# GPS_radiologger_v20_CAM_M8Q_Programmer.net
KiCad netlist of a schematic drawn in EAGLE
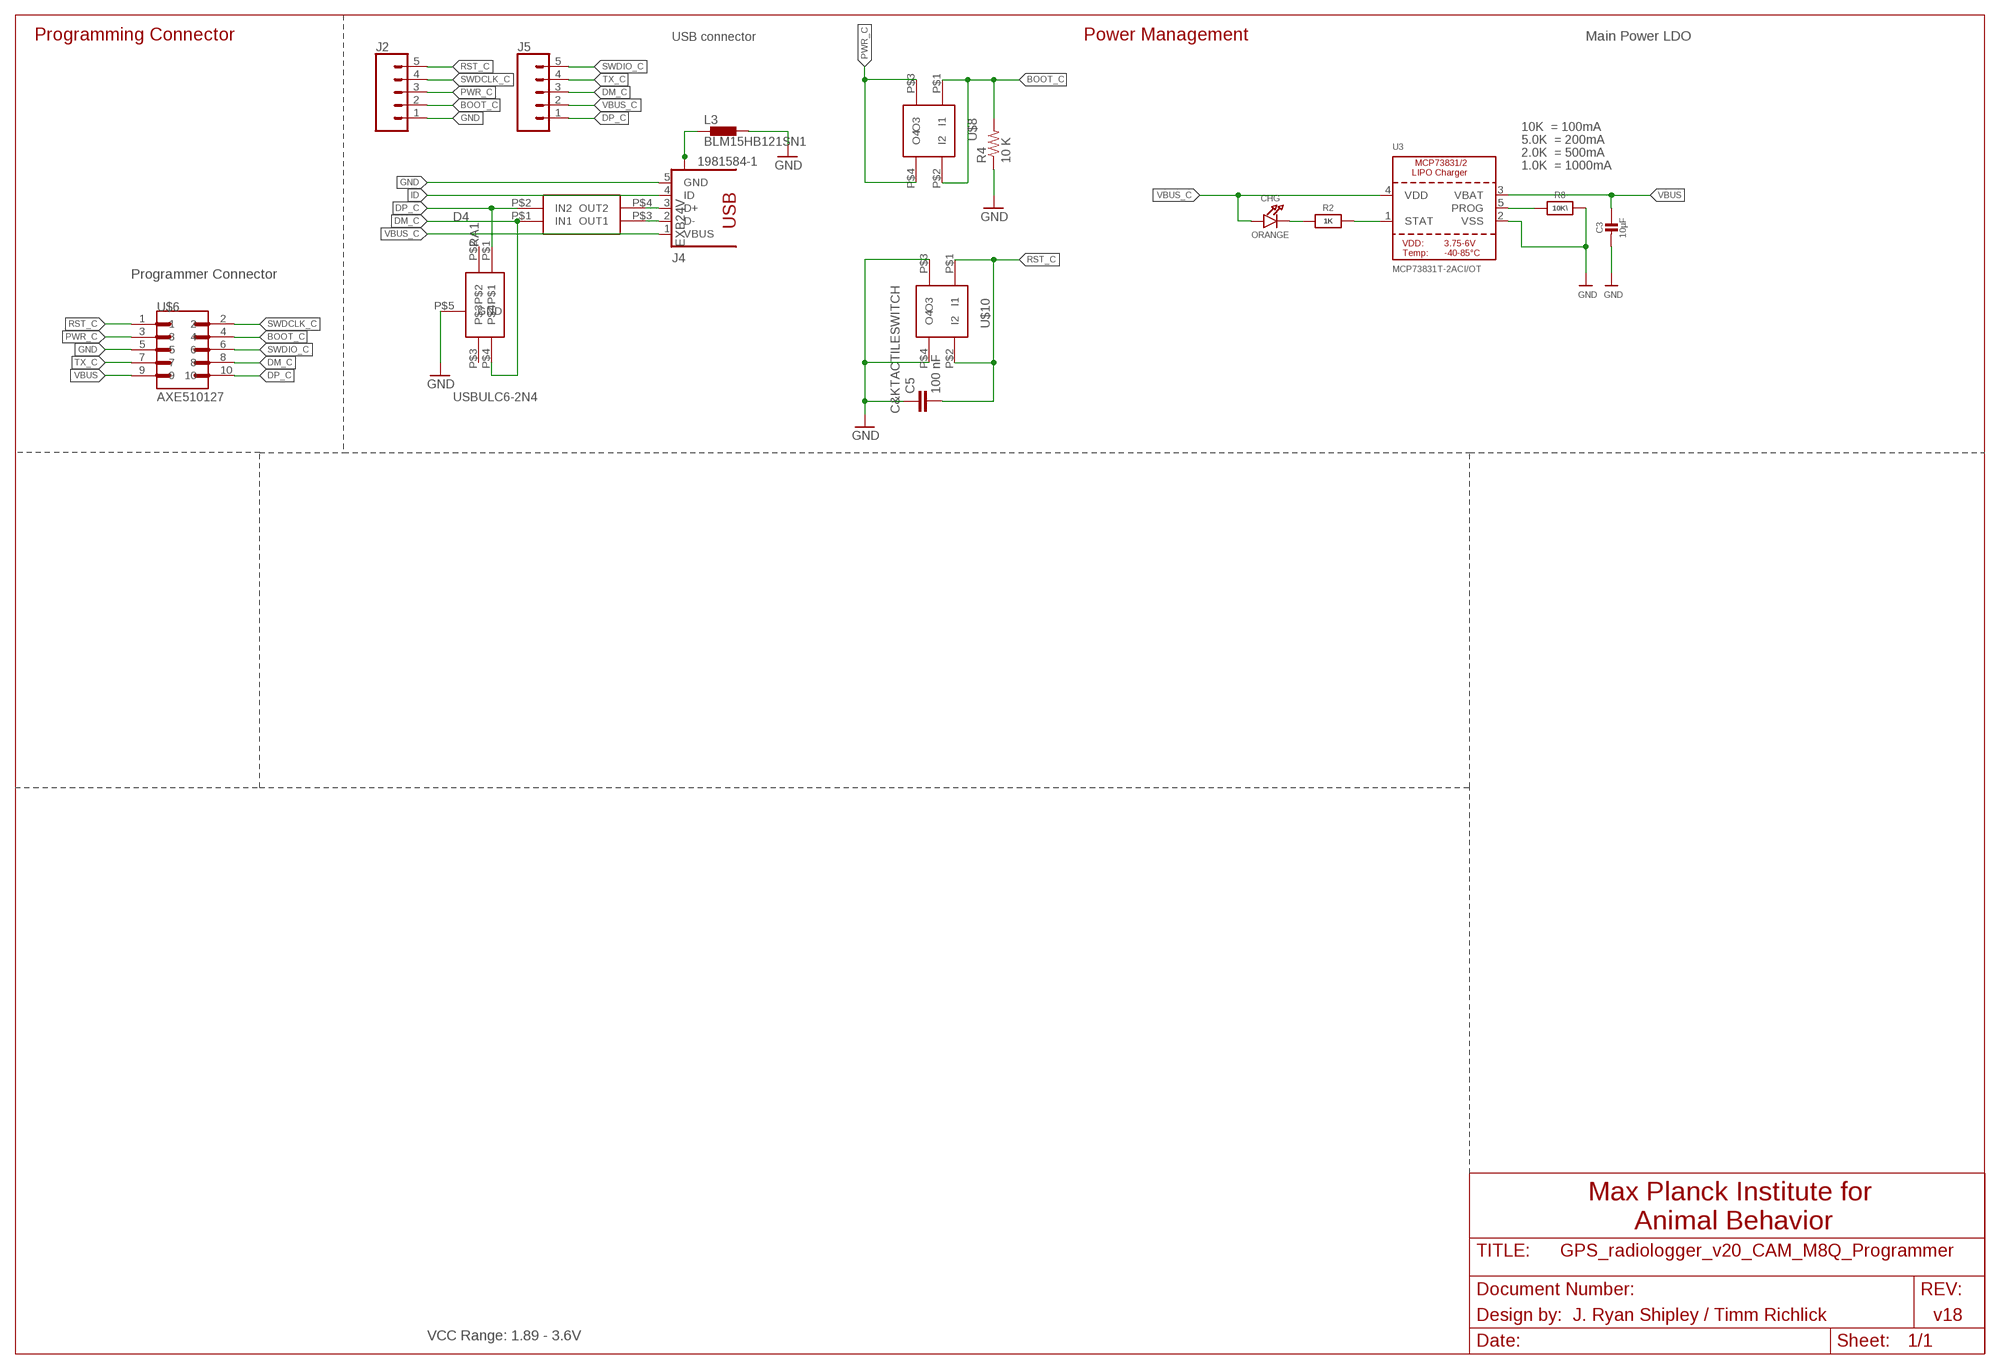
[diagram p0: schematic, sheet 1]

(export (version "E")
  (design (tool "Eeschema 10.0.6"))
  (components
    (comp (ref "C3")
      (value "10µF")
      (footprint "eagle-import:0805-NO")
      (libsource (lib "eagle-import") (part "CAP_CERAMIC0805-NOOUTLINE"))
    )
    (comp (ref "C5")
      (value "100 nF")
      (footprint "eagle-import:0402-CAP")
      (libsource (lib "eagle-import") (part "0402CAP.KW"))
    )
    (comp (ref "CHG")
      (value "ORANGE")
      (footprint "eagle-import:CHIPLED_0805_NOOUTLINE")
      (libsource (lib "eagle-import") (part "LED0805_NOOUTLINE"))
    )
    (comp (ref "D4")
      (value "USBULC6-2N4")
      (footprint "eagle-import:USBULC6-2N4")
      (libsource (lib "eagle-import") (part "USBULC6-2N4"))
    )
    (comp (ref "J2")
      (value "CONN_05")
      (footprint "eagle-import:1X05")
      (libsource (lib "eagle-import") (part "CONN_05"))
    )
    (comp (ref "J4")
      (value "1981584-1")
      (footprint "eagle-import:1981584-1")
      (fields (field (name "MF") "Hirose") (field (name "MPN") "ZX62-AB-5PA(11) "))
      (libsource (lib "eagle-import") (part "1981584-1"))
    )
    (comp (ref "J5")
      (value "CONN_05")
      (footprint "eagle-import:1X05")
      (libsource (lib "eagle-import") (part "CONN_05"))
    )
    (comp (ref "L3")
      (value "BLM15HB121SN1")
      (footprint "eagle-import:0402")
      (libsource (lib "eagle-import") (part "BLM15HB121SN1"))
    )
    (comp (ref "R2")
      (value "1K")
      (footprint "eagle-import:0603-NO")
      (libsource (lib "eagle-import") (part "RESISTOR_0603_NOOUT"))
    )
    (comp (ref "R4")
      (value "10 K")
      (footprint "eagle-import:0402-RES")
      (libsource (lib "eagle-import") (part "0402RES.KW"))
    )
    (comp (ref "R8")
      (value "10K\\")
      (footprint "eagle-import:0603-NO")
      (libsource (lib "eagle-import") (part "RESISTOR_0603_NOOUT"))
    )
    (comp (ref "RA1")
      (value "EXB24V")
      (footprint "eagle-import:EXB24V")
      (libsource (lib "eagle-import") (part "EXB24V"))
    )
    (comp (ref "U$6")
      (value "AXE510127")
      (footprint "eagle-import:AXE510127")
      (libsource (lib "eagle-import") (part "AXE510127"))
    )
    (comp (ref "U$8")
      (value "C&KTACTILESWITCH")
      (footprint "eagle-import:C&KTACTILESWITCH")
      (libsource (lib "eagle-import") (part "C&KTACTILESWITCH"))
    )
    (comp (ref "U$10")
      (value "C&KTACTILESWITCH")
      (footprint "eagle-import:C&KTACTILESWITCH")
      (libsource (lib "eagle-import") (part "C&KTACTILESWITCH"))
    )
    (comp (ref "U3")
      (value "MCP73831T-2ACI/OT")
      (footprint "eagle-import:SOT23-5")
      (libsource (lib "eagle-import") (part "MCP73831/2"))
    )
  )
  (nets
    (net (code "1") (name "BOOT_C") (class "Default")
      (node (ref "J2") (pin "2") (pinfunction "2_2") (pintype "passive"))
      (node (ref "R4") (pin "2") (pinfunction "2_2") (pintype "passive"))
      (node (ref "U$6") (pin "4") (pinfunction "4_4") (pintype "passive"))
      (node (ref "U$8") (pin "P$1") (pinfunction "I1_P$1") (pintype "bidirectional"))
      (node (ref "U$8") (pin "P$2") (pinfunction "I2_P$2") (pintype "bidirectional"))
    )
    (net (code "2") (name "DM_C") (class "Default")
      (node (ref "D4") (pin "P$4") (pinfunction "P$4_P$4") (pintype "bidirectional"))
      (node (ref "J5") (pin "3") (pinfunction "3_3") (pintype "passive"))
      (node (ref "RA1") (pin "P$1") (pinfunction "IN1_P$1") (pintype "bidirectional"))
      (node (ref "U$6") (pin "8") (pinfunction "8_8") (pintype "passive"))
    )
    (net (code "3") (name "DP_C") (class "Default")
      (node (ref "D4") (pin "P$1") (pinfunction "P$1_P$1") (pintype "bidirectional"))
      (node (ref "J5") (pin "1") (pinfunction "1_1") (pintype "passive"))
      (node (ref "RA1") (pin "P$2") (pinfunction "IN2_P$2") (pintype "bidirectional"))
      (node (ref "U$6") (pin "10") (pinfunction "10_10") (pintype "passive"))
    )
    (net (code "4") (name "GND") (class "Default")
      (node (ref "C3") (pin "2") (pinfunction "2_2") (pintype "passive"))
      (node (ref "C5") (pin "1") (pinfunction "1_1") (pintype "passive"))
      (node (ref "D4") (pin "P$5") (pinfunction "GND_P$5") (pintype "bidirectional"))
      (node (ref "J2") (pin "1") (pinfunction "1_1") (pintype "passive"))
      (node (ref "J4") (pin "5") (pinfunction "GND_5") (pintype "passive"))
      (node (ref "L3") (pin "2") (pinfunction "2_2") (pintype "passive"))
      (node (ref "R4") (pin "1") (pinfunction "1_1") (pintype "passive"))
      (node (ref "R8") (pin "2") (pinfunction "2_2") (pintype "passive"))
      (node (ref "U$10") (pin "P$3") (pinfunction "O3_P$3") (pintype "bidirectional"))
      (node (ref "U$10") (pin "P$4") (pinfunction "O4_P$4") (pintype "bidirectional"))
      (node (ref "U$6") (pin "5") (pinfunction "5_5") (pintype "passive"))
      (node (ref "U3") (pin "2") (pinfunction "VSS_2") (pintype "power_in"))
    )
    (net (code "5") (name "ID") (class "Default")
      (node (ref "J4") (pin "4") (pinfunction "ID_4") (pintype "passive"))
    )
    (net (code "6") (name "Net-(CHG-PadC)") (class "Default")
      (node (ref "CHG") (pin "C") (pinfunction "C_C") (pintype "passive"))
      (node (ref "R2") (pin "1") (pinfunction "1_1") (pintype "passive"))
    )
    (net (code "7") (name "Net-(J4-D+)") (class "Default")
      (node (ref "J4") (pin "3") (pinfunction "D+_3") (pintype "passive"))
      (node (ref "RA1") (pin "P$4") (pinfunction "OUT2_P$4") (pintype "bidirectional"))
    )
    (net (code "8") (name "Net-(J4-D-)") (class "Default")
      (node (ref "J4") (pin "2") (pinfunction "D-_2") (pintype "passive"))
      (node (ref "RA1") (pin "P$3") (pinfunction "OUT1_P$3") (pintype "bidirectional"))
    )
    (net (code "9") (name "Net-(J4-PadS1)") (class "Default")
      (node (ref "J4") (pin "S1") (pinfunction "S1_S1") (pintype "passive"))
      (node (ref "J4") (pin "S2") (pinfunction "S2_S2") (pintype "passive"))
      (node (ref "J4") (pin "S3") (pinfunction "S3_S3") (pintype "passive"))
      (node (ref "J4") (pin "S4") (pinfunction "S4_S4") (pintype "passive"))
      (node (ref "L3") (pin "1") (pinfunction "1_1") (pintype "passive"))
    )
    (net (code "10") (name "Net-(U3-PROG)") (class "Default")
      (node (ref "R8") (pin "1") (pinfunction "1_1") (pintype "passive"))
      (node (ref "U3") (pin "5") (pinfunction "PROG_5") (pintype "input"))
    )
    (net (code "11") (name "Net-(U3-STAT)") (class "Default")
      (node (ref "R2") (pin "2") (pinfunction "2_2") (pintype "passive"))
      (node (ref "U3") (pin "1") (pinfunction "STAT_1") (pintype "output"))
    )
    (net (code "12") (name "PWR_C") (class "Default")
      (node (ref "J2") (pin "3") (pinfunction "3_3") (pintype "passive"))
      (node (ref "U$6") (pin "3") (pinfunction "3_3") (pintype "passive"))
      (node (ref "U$8") (pin "P$3") (pinfunction "O3_P$3") (pintype "bidirectional"))
      (node (ref "U$8") (pin "P$4") (pinfunction "O4_P$4") (pintype "bidirectional"))
    )
    (net (code "13") (name "RST_C") (class "Default")
      (node (ref "C5") (pin "2") (pinfunction "2_2") (pintype "passive"))
      (node (ref "J2") (pin "5") (pinfunction "5_5") (pintype "passive"))
      (node (ref "U$10") (pin "P$1") (pinfunction "I1_P$1") (pintype "bidirectional"))
      (node (ref "U$10") (pin "P$2") (pinfunction "I2_P$2") (pintype "bidirectional"))
      (node (ref "U$6") (pin "1") (pinfunction "1_1") (pintype "passive"))
    )
    (net (code "14") (name "SWDCLK_C") (class "Default")
      (node (ref "J2") (pin "4") (pinfunction "4_4") (pintype "passive"))
      (node (ref "U$6") (pin "2") (pinfunction "2_2") (pintype "passive"))
    )
    (net (code "15") (name "SWDIO_C") (class "Default")
      (node (ref "J5") (pin "5") (pinfunction "5_5") (pintype "passive"))
      (node (ref "U$6") (pin "6") (pinfunction "6_6") (pintype "passive"))
    )
    (net (code "16") (name "TX_C") (class "Default")
      (node (ref "J5") (pin "4") (pinfunction "4_4") (pintype "passive"))
      (node (ref "U$6") (pin "7") (pinfunction "7_7") (pintype "passive"))
    )
    (net (code "17") (name "VBUS") (class "Default")
      (node (ref "C3") (pin "1") (pinfunction "1_1") (pintype "passive"))
      (node (ref "U$6") (pin "9") (pinfunction "9_9") (pintype "passive"))
      (node (ref "U3") (pin "3") (pinfunction "VBAT_3") (pintype "power_in"))
    )
    (net (code "18") (name "VBUS_C") (class "Default")
      (node (ref "CHG") (pin "A") (pinfunction "A_A") (pintype "passive"))
      (node (ref "J4") (pin "1") (pinfunction "VBUS_1") (pintype "passive"))
      (node (ref "J5") (pin "2") (pinfunction "2_2") (pintype "passive"))
      (node (ref "U3") (pin "4") (pinfunction "VDD_4") (pintype "power_in"))
    )
    (net (code "19") (name "unconnected-(D4-PadP$2)") (class "Default")
      (node (ref "D4") (pin "P$2") (pinfunction "P$2_P$2") (pintype "bidirectional"))
    )
    (net (code "20") (name "unconnected-(D4-PadP$3)") (class "Default")
      (node (ref "D4") (pin "P$3") (pinfunction "P$3_P$3") (pintype "bidirectional"))
    )
  )
)
